# TDA7429_BREAKOUT.net
KiCad netlist of a schematic drawn in EAGLE
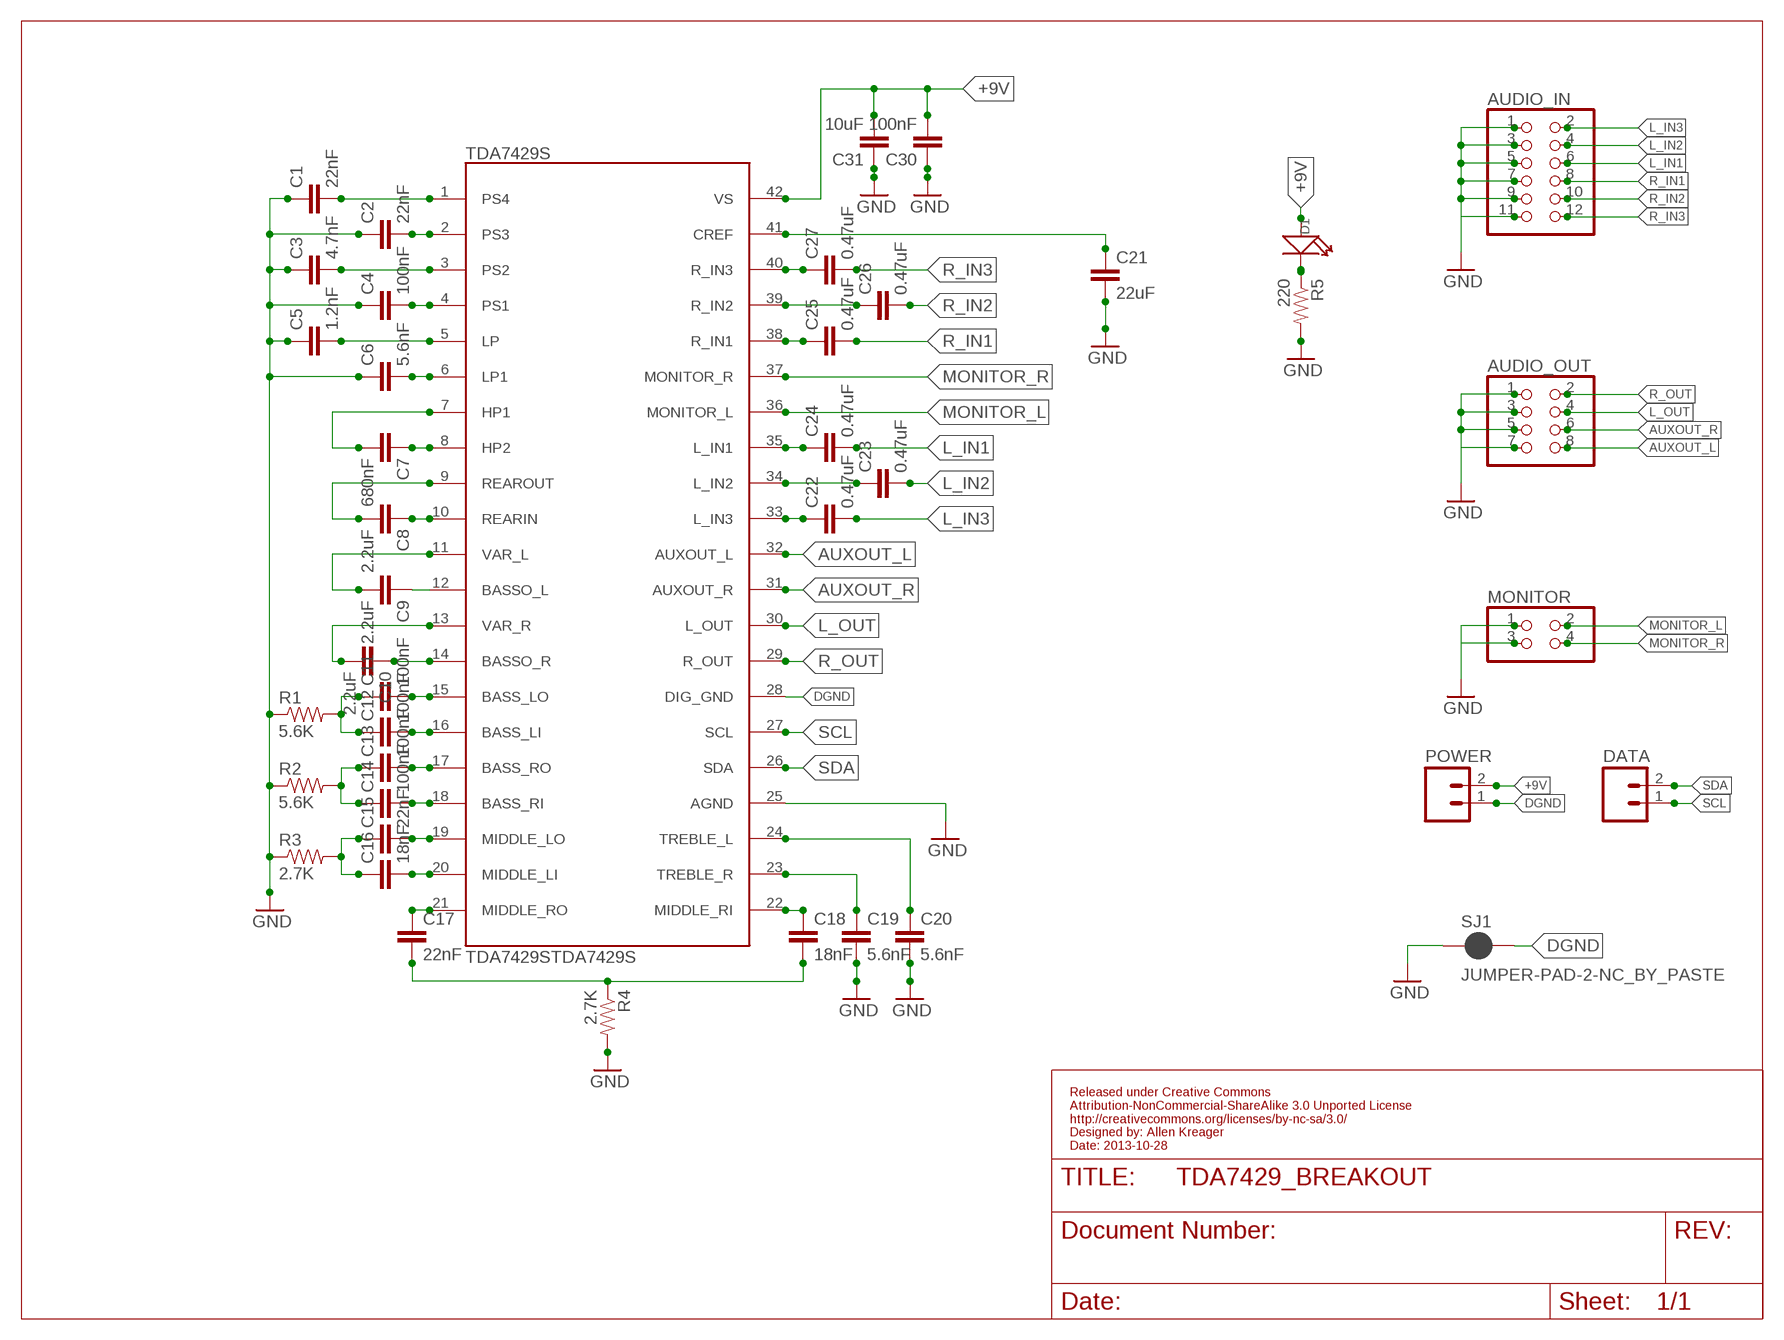
[diagram p0: schematic, sheet 1]

(export (version "E")
  (design (tool "Eeschema 10.0.6"))
  (components
    (comp (ref "AUDIO_IN")
      (value "PINHD-2X6")
      (footprint "eagle-import:2X06")
      (libsource (lib "eagle-import") (part "PINHD-2X6"))
    )
    (comp (ref "AUDIO_OUT")
      (value "PINHD-2X4")
      (footprint "eagle-import:2X04")
      (libsource (lib "eagle-import") (part "PINHD-2X4"))
    )
    (comp (ref "C1")
      (value "22nF")
      (footprint "eagle-import:0805")
      (libsource (lib "eagle-import") (part "CAP0805"))
    )
    (comp (ref "C2")
      (value "22nF")
      (footprint "eagle-import:0805")
      (libsource (lib "eagle-import") (part "CAP0805"))
    )
    (comp (ref "C3")
      (value "4.7nF")
      (footprint "eagle-import:0805")
      (libsource (lib "eagle-import") (part "CAP0805"))
    )
    (comp (ref "C4")
      (value "100nF")
      (footprint "eagle-import:0805")
      (libsource (lib "eagle-import") (part "CAP0805"))
    )
    (comp (ref "C5")
      (value "1.2nF")
      (footprint "eagle-import:0805")
      (libsource (lib "eagle-import") (part "CAP0805"))
    )
    (comp (ref "C6")
      (value "5.6nF")
      (footprint "eagle-import:0805")
      (libsource (lib "eagle-import") (part "CAP0805"))
    )
    (comp (ref "C7")
      (value "680nF")
      (footprint "eagle-import:0805")
      (libsource (lib "eagle-import") (part "CAP0805"))
    )
    (comp (ref "C8")
      (value "2.2uF")
      (footprint "eagle-import:0805")
      (libsource (lib "eagle-import") (part "CAP0805"))
    )
    (comp (ref "C9")
      (value "2.2uF")
      (footprint "eagle-import:0805")
      (libsource (lib "eagle-import") (part "CAP0805"))
    )
    (comp (ref "C10")
      (value "2.2uF")
      (footprint "eagle-import:0805")
      (libsource (lib "eagle-import") (part "CAP0805"))
    )
    (comp (ref "C11")
      (value "100nF")
      (footprint "eagle-import:0805")
      (libsource (lib "eagle-import") (part "CAP0805"))
    )
    (comp (ref "C12")
      (value "100nF")
      (footprint "eagle-import:0805")
      (libsource (lib "eagle-import") (part "CAP0805"))
    )
    (comp (ref "C13")
      (value "100nF")
      (footprint "eagle-import:0805")
      (libsource (lib "eagle-import") (part "CAP0805"))
    )
    (comp (ref "C14")
      (value "100nF")
      (footprint "eagle-import:0805")
      (libsource (lib "eagle-import") (part "CAP0805"))
    )
    (comp (ref "C15")
      (value "22nF")
      (footprint "eagle-import:0805")
      (libsource (lib "eagle-import") (part "CAP0805"))
    )
    (comp (ref "C16")
      (value "18nF")
      (footprint "eagle-import:0805")
      (libsource (lib "eagle-import") (part "CAP0805"))
    )
    (comp (ref "C17")
      (value "22nF")
      (footprint "eagle-import:0805")
      (libsource (lib "eagle-import") (part "CAP0805"))
    )
    (comp (ref "C18")
      (value "18nF")
      (footprint "eagle-import:0805")
      (libsource (lib "eagle-import") (part "CAP0805"))
    )
    (comp (ref "C19")
      (value "5.6nF")
      (footprint "eagle-import:0805")
      (libsource (lib "eagle-import") (part "CAP0805"))
    )
    (comp (ref "C20")
      (value "5.6nF")
      (footprint "eagle-import:0805")
      (libsource (lib "eagle-import") (part "CAP0805"))
    )
    (comp (ref "C21")
      (value "22uF")
      (footprint "eagle-import:0805")
      (libsource (lib "eagle-import") (part "CAP0805"))
    )
    (comp (ref "C22")
      (value "0.47uF")
      (footprint "eagle-import:0805")
      (libsource (lib "eagle-import") (part "CAP0805"))
    )
    (comp (ref "C23")
      (value "0.47uF")
      (footprint "eagle-import:0805")
      (libsource (lib "eagle-import") (part "CAP0805"))
    )
    (comp (ref "C24")
      (value "0.47uF")
      (footprint "eagle-import:0805")
      (libsource (lib "eagle-import") (part "CAP0805"))
    )
    (comp (ref "C25")
      (value "0.47uF")
      (footprint "eagle-import:0805")
      (libsource (lib "eagle-import") (part "CAP0805"))
    )
    (comp (ref "C26")
      (value "0.47uF")
      (footprint "eagle-import:0805")
      (libsource (lib "eagle-import") (part "CAP0805"))
    )
    (comp (ref "C27")
      (value "0.47uF")
      (footprint "eagle-import:0805")
      (libsource (lib "eagle-import") (part "CAP0805"))
    )
    (comp (ref "C30")
      (value "100nF")
      (footprint "eagle-import:0805")
      (libsource (lib "eagle-import") (part "CAP0805"))
    )
    (comp (ref "C31")
      (value "10uF")
      (footprint "eagle-import:0805")
      (libsource (lib "eagle-import") (part "CAP0805"))
    )
    (comp (ref "D1")
      (value "LED")
      (footprint "eagle-import:LED0603")
      (libsource (lib "eagle-import") (part "LED"))
    )
    (comp (ref "DATA")
      (value "M02PTH")
      (footprint "eagle-import:1X02")
      (libsource (lib "eagle-import") (part "M02PTH"))
    )
    (comp (ref "MONITOR")
      (value "PINHD-2X2")
      (footprint "eagle-import:2X02")
      (libsource (lib "eagle-import") (part "PINHD-2X2"))
    )
    (comp (ref "POWER")
      (value "M02PTH")
      (footprint "eagle-import:1X02")
      (libsource (lib "eagle-import") (part "M02PTH"))
    )
    (comp (ref "R1")
      (value "5.6K")
      (footprint "eagle-import:0805")
      (libsource (lib "eagle-import") (part "RESISTOR0805-RES"))
    )
    (comp (ref "R2")
      (value "5.6K")
      (footprint "eagle-import:0805")
      (libsource (lib "eagle-import") (part "RESISTOR0805-RES"))
    )
    (comp (ref "R3")
      (value "2.7K")
      (footprint "eagle-import:0805")
      (libsource (lib "eagle-import") (part "RESISTOR0805-RES"))
    )
    (comp (ref "R4")
      (value "2.7K")
      (footprint "eagle-import:0805")
      (libsource (lib "eagle-import") (part "RESISTOR0805-RES"))
    )
    (comp (ref "R5")
      (value "220")
      (footprint "eagle-import:0805")
      (libsource (lib "eagle-import") (part "RESISTOR0805-RES"))
    )
    (comp (ref "SJ1")
      (value "JUMPER-PAD-2-NC_BY_PASTE")
      (footprint "eagle-import:PAD-JUMPER-2-NC_BY_PASTE_YES_SILK")
      (libsource (lib "eagle-import") (part "JUMPER-PAD-2-NC_BY_PASTE"))
    )
    (comp (ref "TDA7429S")
      (value "TDA7429STDA7429S")
      (footprint "eagle-import:SDIP42")
      (libsource (lib "eagle-import") (part "TDA7429STDA7429S"))
    )
  )
  (nets
    (net (code "1") (name "+9V") (class "Default")
      (node (ref "C30") (pin "2") (pinfunction "2_2") (pintype "passive"))
      (node (ref "C31") (pin "2") (pinfunction "2_2") (pintype "passive"))
      (node (ref "D1") (pin "+") (pinfunction "+_+") (pintype "passive"))
      (node (ref "POWER") (pin "2") (pinfunction "2_2") (pintype "passive"))
      (node (ref "TDA7429S") (pin "42") (pinfunction "VS_42") (pintype "bidirectional"))
    )
    (net (code "2") (name "AUXOUT_L") (class "Default")
      (node (ref "AUDIO_OUT") (pin "8") (pinfunction "8_8") (pintype "passive"))
      (node (ref "TDA7429S") (pin "32") (pinfunction "AUXOUT_L_32") (pintype "bidirectional"))
    )
    (net (code "3") (name "AUXOUT_R") (class "Default")
      (node (ref "AUDIO_OUT") (pin "6") (pinfunction "6_6") (pintype "passive"))
      (node (ref "TDA7429S") (pin "31") (pinfunction "AUXOUT_R_31") (pintype "bidirectional"))
    )
    (net (code "4") (name "DGND") (class "Default")
      (node (ref "POWER") (pin "1") (pinfunction "1_1") (pintype "passive"))
      (node (ref "SJ1") (pin "2") (pinfunction "2_2") (pintype "passive"))
      (node (ref "TDA7429S") (pin "28") (pinfunction "DIG_GND_28") (pintype "bidirectional"))
    )
    (net (code "5") (name "GND") (class "Default")
      (node (ref "AUDIO_IN") (pin "1") (pinfunction "1_1") (pintype "passive"))
      (node (ref "AUDIO_IN") (pin "11") (pinfunction "11_11") (pintype "passive"))
      (node (ref "AUDIO_IN") (pin "3") (pinfunction "3_3") (pintype "passive"))
      (node (ref "AUDIO_IN") (pin "5") (pinfunction "5_5") (pintype "passive"))
      (node (ref "AUDIO_IN") (pin "7") (pinfunction "7_7") (pintype "passive"))
      (node (ref "AUDIO_IN") (pin "9") (pinfunction "9_9") (pintype "passive"))
      (node (ref "AUDIO_OUT") (pin "1") (pinfunction "1_1") (pintype "passive"))
      (node (ref "AUDIO_OUT") (pin "3") (pinfunction "3_3") (pintype "passive"))
      (node (ref "AUDIO_OUT") (pin "5") (pinfunction "5_5") (pintype "passive"))
      (node (ref "AUDIO_OUT") (pin "7") (pinfunction "7_7") (pintype "passive"))
      (node (ref "C1") (pin "1") (pinfunction "1_1") (pintype "passive"))
      (node (ref "C19") (pin "2") (pinfunction "2_2") (pintype "passive"))
      (node (ref "C2") (pin "1") (pinfunction "1_1") (pintype "passive"))
      (node (ref "C20") (pin "2") (pinfunction "2_2") (pintype "passive"))
      (node (ref "C21") (pin "2") (pinfunction "2_2") (pintype "passive"))
      (node (ref "C3") (pin "1") (pinfunction "1_1") (pintype "passive"))
      (node (ref "C30") (pin "1") (pinfunction "1_1") (pintype "passive"))
      (node (ref "C31") (pin "1") (pinfunction "1_1") (pintype "passive"))
      (node (ref "C4") (pin "1") (pinfunction "1_1") (pintype "passive"))
      (node (ref "C5") (pin "1") (pinfunction "1_1") (pintype "passive"))
      (node (ref "C6") (pin "1") (pinfunction "1_1") (pintype "passive"))
      (node (ref "MONITOR") (pin "1") (pinfunction "1_1") (pintype "passive"))
      (node (ref "MONITOR") (pin "3") (pinfunction "3_3") (pintype "passive"))
      (node (ref "R1") (pin "1") (pinfunction "1_1") (pintype "passive"))
      (node (ref "R2") (pin "1") (pinfunction "1_1") (pintype "passive"))
      (node (ref "R3") (pin "1") (pinfunction "1_1") (pintype "passive"))
      (node (ref "R4") (pin "2") (pinfunction "2_2") (pintype "passive"))
      (node (ref "R5") (pin "2") (pinfunction "2_2") (pintype "passive"))
      (node (ref "SJ1") (pin "1") (pinfunction "1_1") (pintype "passive"))
      (node (ref "TDA7429S") (pin "25") (pinfunction "AGND_25") (pintype "bidirectional"))
    )
    (net (code "6") (name "L_IN1") (class "Default")
      (node (ref "AUDIO_IN") (pin "6") (pinfunction "6_6") (pintype "passive"))
      (node (ref "C24") (pin "2") (pinfunction "2_2") (pintype "passive"))
    )
    (net (code "7") (name "L_IN2") (class "Default")
      (node (ref "AUDIO_IN") (pin "4") (pinfunction "4_4") (pintype "passive"))
      (node (ref "C23") (pin "2") (pinfunction "2_2") (pintype "passive"))
    )
    (net (code "8") (name "L_IN3") (class "Default")
      (node (ref "AUDIO_IN") (pin "2") (pinfunction "2_2") (pintype "passive"))
      (node (ref "C22") (pin "2") (pinfunction "2_2") (pintype "passive"))
    )
    (net (code "9") (name "L_OUT") (class "Default")
      (node (ref "AUDIO_OUT") (pin "4") (pinfunction "4_4") (pintype "passive"))
      (node (ref "TDA7429S") (pin "30") (pinfunction "L_OUT_30") (pintype "bidirectional"))
    )
    (net (code "10") (name "MONITOR_L") (class "Default")
      (node (ref "MONITOR") (pin "2") (pinfunction "2_2") (pintype "passive"))
      (node (ref "TDA7429S") (pin "36") (pinfunction "MONITOR_L_36") (pintype "bidirectional"))
    )
    (net (code "11") (name "MONITOR_R") (class "Default")
      (node (ref "MONITOR") (pin "4") (pinfunction "4_4") (pintype "passive"))
      (node (ref "TDA7429S") (pin "37") (pinfunction "MONITOR_R_37") (pintype "bidirectional"))
    )
    (net (code "12") (name "Net-(C11-Pad1)") (class "Default")
      (node (ref "C11") (pin "1") (pinfunction "1_1") (pintype "passive"))
      (node (ref "C12") (pin "1") (pinfunction "1_1") (pintype "passive"))
      (node (ref "R1") (pin "2") (pinfunction "2_2") (pintype "passive"))
    )
    (net (code "13") (name "Net-(C13-Pad1)") (class "Default")
      (node (ref "C13") (pin "1") (pinfunction "1_1") (pintype "passive"))
      (node (ref "C14") (pin "1") (pinfunction "1_1") (pintype "passive"))
      (node (ref "R2") (pin "2") (pinfunction "2_2") (pintype "passive"))
    )
    (net (code "14") (name "Net-(C15-Pad1)") (class "Default")
      (node (ref "C15") (pin "1") (pinfunction "1_1") (pintype "passive"))
      (node (ref "C16") (pin "1") (pinfunction "1_1") (pintype "passive"))
      (node (ref "R3") (pin "2") (pinfunction "2_2") (pintype "passive"))
    )
    (net (code "15") (name "Net-(C17-Pad2)") (class "Default")
      (node (ref "C17") (pin "2") (pinfunction "2_2") (pintype "passive"))
      (node (ref "C18") (pin "2") (pinfunction "2_2") (pintype "passive"))
      (node (ref "R4") (pin "1") (pinfunction "1_1") (pintype "passive"))
    )
    (net (code "16") (name "Net-(D1-Pad-)") (class "Default")
      (node (ref "D1") (pin "-") (pinfunction "-_-") (pintype "passive"))
      (node (ref "R5") (pin "1") (pinfunction "1_1") (pintype "passive"))
    )
    (net (code "17") (name "Net-(TDA7429S-BASSO_L)") (class "Default")
      (node (ref "C9") (pin "1") (pinfunction "1_1") (pintype "passive"))
      (node (ref "TDA7429S") (pin "12") (pinfunction "BASSO_L_12") (pintype "bidirectional"))
    )
    (net (code "18") (name "Net-(TDA7429S-BASSO_R)") (class "Default")
      (node (ref "C10") (pin "1") (pinfunction "1_1") (pintype "passive"))
      (node (ref "TDA7429S") (pin "14") (pinfunction "BASSO_R_14") (pintype "bidirectional"))
    )
    (net (code "19") (name "Net-(TDA7429S-BASS_LI)") (class "Default")
      (node (ref "C12") (pin "2") (pinfunction "2_2") (pintype "passive"))
      (node (ref "TDA7429S") (pin "16") (pinfunction "BASS_LI_16") (pintype "bidirectional"))
    )
    (net (code "20") (name "Net-(TDA7429S-BASS_LO)") (class "Default")
      (node (ref "C11") (pin "2") (pinfunction "2_2") (pintype "passive"))
      (node (ref "TDA7429S") (pin "15") (pinfunction "BASS_LO_15") (pintype "bidirectional"))
    )
    (net (code "21") (name "Net-(TDA7429S-BASS_RI)") (class "Default")
      (node (ref "C14") (pin "2") (pinfunction "2_2") (pintype "passive"))
      (node (ref "TDA7429S") (pin "18") (pinfunction "BASS_RI_18") (pintype "bidirectional"))
    )
    (net (code "22") (name "Net-(TDA7429S-BASS_RO)") (class "Default")
      (node (ref "C13") (pin "2") (pinfunction "2_2") (pintype "passive"))
      (node (ref "TDA7429S") (pin "17") (pinfunction "BASS_RO_17") (pintype "bidirectional"))
    )
    (net (code "23") (name "Net-(TDA7429S-CREF)") (class "Default")
      (node (ref "C21") (pin "1") (pinfunction "1_1") (pintype "passive"))
      (node (ref "TDA7429S") (pin "41") (pinfunction "CREF_41") (pintype "bidirectional"))
    )
    (net (code "24") (name "Net-(TDA7429S-HP1)") (class "Default")
      (node (ref "C7") (pin "2") (pinfunction "2_2") (pintype "passive"))
      (node (ref "TDA7429S") (pin "7") (pinfunction "HP1_7") (pintype "bidirectional"))
    )
    (net (code "25") (name "Net-(TDA7429S-HP2)") (class "Default")
      (node (ref "C7") (pin "1") (pinfunction "1_1") (pintype "passive"))
      (node (ref "TDA7429S") (pin "8") (pinfunction "HP2_8") (pintype "bidirectional"))
    )
    (net (code "26") (name "Net-(TDA7429S-LP)") (class "Default")
      (node (ref "C5") (pin "2") (pinfunction "2_2") (pintype "passive"))
      (node (ref "TDA7429S") (pin "5") (pinfunction "LP_5") (pintype "bidirectional"))
    )
    (net (code "27") (name "Net-(TDA7429S-LP1)") (class "Default")
      (node (ref "C6") (pin "2") (pinfunction "2_2") (pintype "passive"))
      (node (ref "TDA7429S") (pin "6") (pinfunction "LP1_6") (pintype "bidirectional"))
    )
    (net (code "28") (name "Net-(TDA7429S-L_IN1)") (class "Default")
      (node (ref "C24") (pin "1") (pinfunction "1_1") (pintype "passive"))
      (node (ref "TDA7429S") (pin "35") (pinfunction "L_IN1_35") (pintype "bidirectional"))
    )
    (net (code "29") (name "Net-(TDA7429S-L_IN2)") (class "Default")
      (node (ref "C23") (pin "1") (pinfunction "1_1") (pintype "passive"))
      (node (ref "TDA7429S") (pin "34") (pinfunction "L_IN2_34") (pintype "bidirectional"))
    )
    (net (code "30") (name "Net-(TDA7429S-L_IN3)") (class "Default")
      (node (ref "C22") (pin "1") (pinfunction "1_1") (pintype "passive"))
      (node (ref "TDA7429S") (pin "33") (pinfunction "L_IN3_33") (pintype "bidirectional"))
    )
    (net (code "31") (name "Net-(TDA7429S-MIDDLE_LI)") (class "Default")
      (node (ref "C16") (pin "2") (pinfunction "2_2") (pintype "passive"))
      (node (ref "TDA7429S") (pin "20") (pinfunction "MIDDLE_LI_20") (pintype "bidirectional"))
    )
    (net (code "32") (name "Net-(TDA7429S-MIDDLE_LO)") (class "Default")
      (node (ref "C15") (pin "2") (pinfunction "2_2") (pintype "passive"))
      (node (ref "TDA7429S") (pin "19") (pinfunction "MIDDLE_LO_19") (pintype "bidirectional"))
    )
    (net (code "33") (name "Net-(TDA7429S-MIDDLE_RI)") (class "Default")
      (node (ref "C18") (pin "1") (pinfunction "1_1") (pintype "passive"))
      (node (ref "TDA7429S") (pin "22") (pinfunction "MIDDLE_RI_22") (pintype "bidirectional"))
    )
    (net (code "34") (name "Net-(TDA7429S-MIDDLE_RO)") (class "Default")
      (node (ref "C17") (pin "1") (pinfunction "1_1") (pintype "passive"))
      (node (ref "TDA7429S") (pin "21") (pinfunction "MIDDLE_RO_21") (pintype "bidirectional"))
    )
    (net (code "35") (name "Net-(TDA7429S-PS1)") (class "Default")
      (node (ref "C4") (pin "2") (pinfunction "2_2") (pintype "passive"))
      (node (ref "TDA7429S") (pin "4") (pinfunction "PS1_4") (pintype "bidirectional"))
    )
    (net (code "36") (name "Net-(TDA7429S-PS2)") (class "Default")
      (node (ref "C3") (pin "2") (pinfunction "2_2") (pintype "passive"))
      (node (ref "TDA7429S") (pin "3") (pinfunction "PS2_3") (pintype "bidirectional"))
    )
    (net (code "37") (name "Net-(TDA7429S-PS3)") (class "Default")
      (node (ref "C2") (pin "2") (pinfunction "2_2") (pintype "passive"))
      (node (ref "TDA7429S") (pin "2") (pinfunction "PS3_2") (pintype "bidirectional"))
    )
    (net (code "38") (name "Net-(TDA7429S-PS4)") (class "Default")
      (node (ref "C1") (pin "2") (pinfunction "2_2") (pintype "passive"))
      (node (ref "TDA7429S") (pin "1") (pinfunction "PS4_1") (pintype "bidirectional"))
    )
    (net (code "39") (name "Net-(TDA7429S-REARIN)") (class "Default")
      (node (ref "C8") (pin "1") (pinfunction "1_1") (pintype "passive"))
      (node (ref "TDA7429S") (pin "10") (pinfunction "REARIN_10") (pintype "bidirectional"))
    )
    (net (code "40") (name "Net-(TDA7429S-REAROUT)") (class "Default")
      (node (ref "C8") (pin "2") (pinfunction "2_2") (pintype "passive"))
      (node (ref "TDA7429S") (pin "9") (pinfunction "REAROUT_9") (pintype "bidirectional"))
    )
    (net (code "41") (name "Net-(TDA7429S-R_IN1)") (class "Default")
      (node (ref "C25") (pin "1") (pinfunction "1_1") (pintype "passive"))
      (node (ref "TDA7429S") (pin "38") (pinfunction "R_IN1_38") (pintype "bidirectional"))
    )
    (net (code "42") (name "Net-(TDA7429S-R_IN2)") (class "Default")
      (node (ref "C26") (pin "1") (pinfunction "1_1") (pintype "passive"))
      (node (ref "TDA7429S") (pin "39") (pinfunction "R_IN2_39") (pintype "bidirectional"))
    )
    (net (code "43") (name "Net-(TDA7429S-R_IN3)") (class "Default")
      (node (ref "C27") (pin "1") (pinfunction "1_1") (pintype "passive"))
      (node (ref "TDA7429S") (pin "40") (pinfunction "R_IN3_40") (pintype "bidirectional"))
    )
    (net (code "44") (name "Net-(TDA7429S-TREBLE_L)") (class "Default")
      (node (ref "C20") (pin "1") (pinfunction "1_1") (pintype "passive"))
      (node (ref "TDA7429S") (pin "24") (pinfunction "TREBLE_L_24") (pintype "bidirectional"))
    )
    (net (code "45") (name "Net-(TDA7429S-TREBLE_R)") (class "Default")
      (node (ref "C19") (pin "1") (pinfunction "1_1") (pintype "passive"))
      (node (ref "TDA7429S") (pin "23") (pinfunction "TREBLE_R_23") (pintype "bidirectional"))
    )
    (net (code "46") (name "Net-(TDA7429S-VAR_L)") (class "Default")
      (node (ref "C9") (pin "2") (pinfunction "2_2") (pintype "passive"))
      (node (ref "TDA7429S") (pin "11") (pinfunction "VAR_L_11") (pintype "bidirectional"))
    )
    (net (code "47") (name "Net-(TDA7429S-VAR_R)") (class "Default")
      (node (ref "C10") (pin "2") (pinfunction "2_2") (pintype "passive"))
      (node (ref "TDA7429S") (pin "13") (pinfunction "VAR_R_13") (pintype "bidirectional"))
    )
    (net (code "48") (name "R_IN1") (class "Default")
      (node (ref "AUDIO_IN") (pin "8") (pinfunction "8_8") (pintype "passive"))
      (node (ref "C25") (pin "2") (pinfunction "2_2") (pintype "passive"))
    )
    (net (code "49") (name "R_IN2") (class "Default")
      (node (ref "AUDIO_IN") (pin "10") (pinfunction "10_10") (pintype "passive"))
      (node (ref "C26") (pin "2") (pinfunction "2_2") (pintype "passive"))
    )
    (net (code "50") (name "R_IN3") (class "Default")
      (node (ref "AUDIO_IN") (pin "12") (pinfunction "12_12") (pintype "passive"))
      (node (ref "C27") (pin "2") (pinfunction "2_2") (pintype "passive"))
    )
    (net (code "51") (name "R_OUT") (class "Default")
      (node (ref "AUDIO_OUT") (pin "2") (pinfunction "2_2") (pintype "passive"))
      (node (ref "TDA7429S") (pin "29") (pinfunction "R_OUT_29") (pintype "bidirectional"))
    )
    (net (code "52") (name "SCL") (class "Default")
      (node (ref "DATA") (pin "1") (pinfunction "1_1") (pintype "passive"))
      (node (ref "TDA7429S") (pin "27") (pinfunction "SCL_27") (pintype "bidirectional"))
    )
    (net (code "53") (name "SDA") (class "Default")
      (node (ref "DATA") (pin "2") (pinfunction "2_2") (pintype "passive"))
      (node (ref "TDA7429S") (pin "26") (pinfunction "SDA_26") (pintype "bidirectional"))
    )
  )
)
